# ZsenzorNou.net
KiCad netlist of a schematic drawn in EAGLE
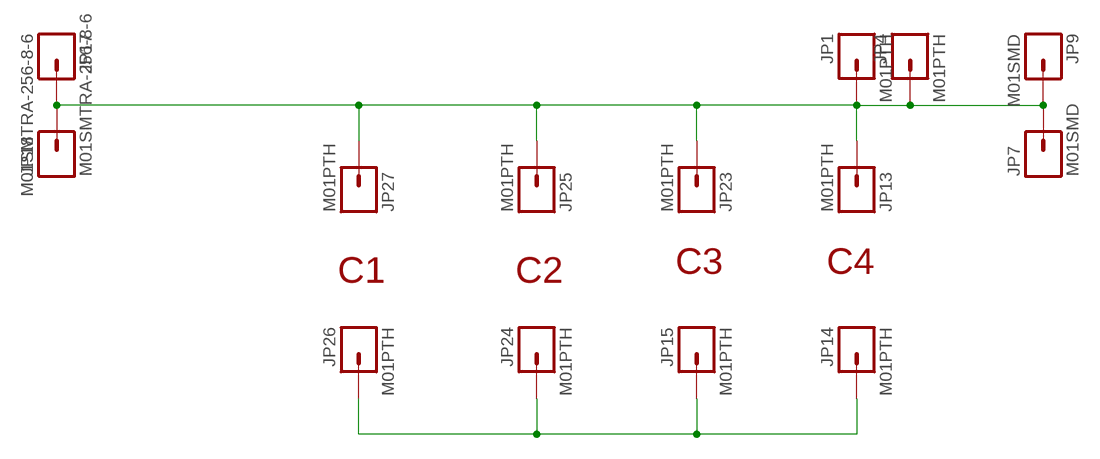
[diagram p0: schematic, sheet 1]

(export (version "E")
  (design (tool "Eeschema 10.0.6"))
  (components
    (comp (ref "JP1")
      (value "M01PTH")
      (footprint "eagle-import:1X01")
      (libsource (lib "eagle-import") (part "M01PTH"))
    )
    (comp (ref "JP4")
      (value "M01PTH")
      (footprint "eagle-import:1X01")
      (libsource (lib "eagle-import") (part "M01PTH"))
    )
    (comp (ref "JP7")
      (value "M01SMD")
      (footprint "eagle-import:LUXEON-PAD")
      (libsource (lib "eagle-import") (part "M01SMD"))
    )
    (comp (ref "JP9")
      (value "M01SMD")
      (footprint "eagle-import:LUXEON-PAD")
      (libsource (lib "eagle-import") (part "M01SMD"))
    )
    (comp (ref "JP13")
      (value "M01PTH")
      (footprint "eagle-import:1X01")
      (libsource (lib "eagle-import") (part "M01PTH"))
    )
    (comp (ref "JP14")
      (value "M01PTH")
      (footprint "eagle-import:1X01")
      (libsource (lib "eagle-import") (part "M01PTH"))
    )
    (comp (ref "JP15")
      (value "M01PTH")
      (footprint "eagle-import:1X01")
      (libsource (lib "eagle-import") (part "M01PTH"))
    )
    (comp (ref "JP17")
      (value "M01SMTRA-256-8-6")
      (footprint "eagle-import:SMTRA-256-8-6")
      (libsource (lib "eagle-import") (part "M01SMTRA-256-8-6"))
    )
    (comp (ref "JP18")
      (value "M01SMTRA-256-8-6")
      (footprint "eagle-import:SMTRA-256-8-6")
      (libsource (lib "eagle-import") (part "M01SMTRA-256-8-6"))
    )
    (comp (ref "JP23")
      (value "M01PTH")
      (footprint "eagle-import:1X01")
      (libsource (lib "eagle-import") (part "M01PTH"))
    )
    (comp (ref "JP24")
      (value "M01PTH")
      (footprint "eagle-import:1X01")
      (libsource (lib "eagle-import") (part "M01PTH"))
    )
    (comp (ref "JP25")
      (value "M01PTH")
      (footprint "eagle-import:1X01")
      (libsource (lib "eagle-import") (part "M01PTH"))
    )
    (comp (ref "JP26")
      (value "M01PTH")
      (footprint "eagle-import:1X01")
      (libsource (lib "eagle-import") (part "M01PTH"))
    )
    (comp (ref "JP27")
      (value "M01PTH")
      (footprint "eagle-import:1X01")
      (libsource (lib "eagle-import") (part "M01PTH"))
    )
  )
  (nets
    (net (code "1") (name "Net-(JP14-Pad1)") (class "Default")
      (node (ref "JP14") (pin "1") (pinfunction "1_1") (pintype "passive"))
      (node (ref "JP15") (pin "1") (pinfunction "1_1") (pintype "passive"))
      (node (ref "JP24") (pin "1") (pinfunction "1_1") (pintype "passive"))
      (node (ref "JP26") (pin "1") (pinfunction "1_1") (pintype "passive"))
    )
    (net (code "2") (name "Net-(JP17-1)") (class "Default")
      (node (ref "JP1") (pin "1") (pinfunction "1_1") (pintype "passive"))
      (node (ref "JP13") (pin "1") (pinfunction "1_1") (pintype "passive"))
      (node (ref "JP17") (pin "P$1") (pinfunction "1_P$1") (pintype "passive"))
      (node (ref "JP18") (pin "P$1") (pinfunction "1_P$1") (pintype "passive"))
      (node (ref "JP23") (pin "1") (pinfunction "1_1") (pintype "passive"))
      (node (ref "JP25") (pin "1") (pinfunction "1_1") (pintype "passive"))
      (node (ref "JP27") (pin "1") (pinfunction "1_1") (pintype "passive"))
      (node (ref "JP4") (pin "1") (pinfunction "1_1") (pintype "passive"))
      (node (ref "JP7") (pin "P$1") (pinfunction "1_P$1") (pintype "passive"))
      (node (ref "JP9") (pin "P$1") (pinfunction "1_P$1") (pintype "passive"))
    )
  )
)
